# dronetester.net
KiCad netlist of a schematic drawn in EAGLE
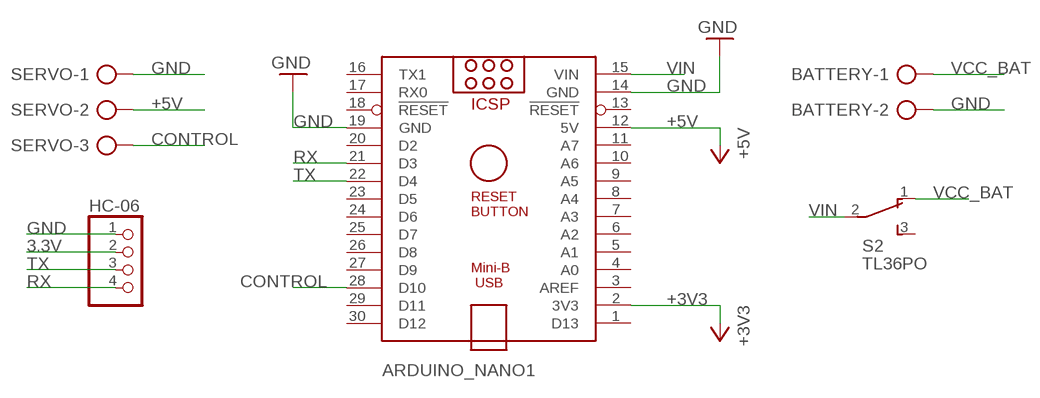
[diagram p0: schematic, sheet 1]

(export (version "E")
  (design (tool "Eeschema 10.0.6"))
  (components
    (comp (ref "ARDUINO_NANO1")
      (value "ARDUINO_NANO")
      (footprint "eagle-import:ARDUINO_NANO")
      (libsource (lib "eagle-import") (part "ARDUINO_NANO"))
    )
    (comp (ref "BATTERY")
      (value "AK500/2-H")
      (footprint "eagle-import:AK500_2-H")
      (libsource (lib "eagle-import") (part "AK500/2-H"))
    )
    (comp (ref "HC-06")
      (value "PINHD-1X4")
      (footprint "eagle-import:1X04")
      (libsource (lib "eagle-import") (part "PINHD-1X4"))
    )
    (comp (ref "S2")
      (value "TL36PO")
      (footprint "eagle-import:TL3XPO")
      (libsource (lib "eagle-import") (part "TL36PO"))
    )
    (comp (ref "SERVO")
      (value "AK500/3-H")
      (footprint "eagle-import:AK500_3-H")
      (libsource (lib "eagle-import") (part "AK500/3-H"))
    )
  )
  (nets
    (net (code "1") (name "+3V3") (class "Default")
      (node (ref "ARDUINO_NANO1") (pin "2") (pinfunction "3V3_2") (pintype "output"))
    )
    (net (code "2") (name "+5V") (class "Default")
      (node (ref "ARDUINO_NANO1") (pin "12") (pinfunction "5V_12") (pintype "power_in"))
      (node (ref "SERVO") (pin "2") (pinfunction "KL_2") (pintype "passive"))
    )
    (net (code "3") (name "/3.3V") (class "Default")
      (node (ref "HC-06") (pin "2") (pinfunction "2_2") (pintype "passive"))
    )
    (net (code "4") (name "/CONTROL") (class "Default")
      (node (ref "ARDUINO_NANO1") (pin "28") (pinfunction "D10_28") (pintype "bidirectional"))
      (node (ref "SERVO") (pin "3") (pinfunction "KL_3") (pintype "passive"))
    )
    (net (code "5") (name "/RX") (class "Default")
      (node (ref "ARDUINO_NANO1") (pin "21") (pinfunction "D3_21") (pintype "bidirectional"))
      (node (ref "HC-06") (pin "4") (pinfunction "4_4") (pintype "passive"))
    )
    (net (code "6") (name "/TX") (class "Default")
      (node (ref "ARDUINO_NANO1") (pin "22") (pinfunction "D4_22") (pintype "bidirectional"))
      (node (ref "HC-06") (pin "3") (pinfunction "3_3") (pintype "passive"))
    )
    (net (code "7") (name "/VCC_BAT") (class "Default")
      (node (ref "BATTERY") (pin "1") (pinfunction "KL_1") (pintype "passive"))
      (node (ref "S2") (pin "1") (pinfunction "O_1") (pintype "passive"))
    )
    (net (code "8") (name "/VIN") (class "Default")
      (node (ref "ARDUINO_NANO1") (pin "15") (pinfunction "VIN_15") (pintype "power_in"))
      (node (ref "S2") (pin "2") (pinfunction "P_2") (pintype "passive"))
    )
    (net (code "9") (name "GND") (class "Default")
      (node (ref "ARDUINO_NANO1") (pin "14") (pinfunction "GND_14") (pintype "power_in"))
      (node (ref "ARDUINO_NANO1") (pin "19") (pinfunction "GND_19") (pintype "power_in"))
      (node (ref "BATTERY") (pin "2") (pinfunction "KL_2") (pintype "passive"))
      (node (ref "HC-06") (pin "1") (pinfunction "1_1") (pintype "passive"))
      (node (ref "SERVO") (pin "1") (pinfunction "KL_1") (pintype "passive"))
    )
    (net (code "10") (name "unconnected-(ARDUINO_NANO1-A0-Pad4)") (class "Default")
      (node (ref "ARDUINO_NANO1") (pin "4") (pinfunction "A0_4") (pintype "bidirectional"))
    )
    (net (code "11") (name "unconnected-(ARDUINO_NANO1-A1-Pad5)") (class "Default")
      (node (ref "ARDUINO_NANO1") (pin "5") (pinfunction "A1_5") (pintype "bidirectional"))
    )
    (net (code "12") (name "unconnected-(ARDUINO_NANO1-A2-Pad6)") (class "Default")
      (node (ref "ARDUINO_NANO1") (pin "6") (pinfunction "A2_6") (pintype "bidirectional"))
    )
    (net (code "13") (name "unconnected-(ARDUINO_NANO1-A3-Pad7)") (class "Default")
      (node (ref "ARDUINO_NANO1") (pin "7") (pinfunction "A3_7") (pintype "bidirectional"))
    )
    (net (code "14") (name "unconnected-(ARDUINO_NANO1-A4-Pad8)") (class "Default")
      (node (ref "ARDUINO_NANO1") (pin "8") (pinfunction "A4_8") (pintype "bidirectional"))
    )
    (net (code "15") (name "unconnected-(ARDUINO_NANO1-A5-Pad9)") (class "Default")
      (node (ref "ARDUINO_NANO1") (pin "9") (pinfunction "A5_9") (pintype "bidirectional"))
    )
    (net (code "16") (name "unconnected-(ARDUINO_NANO1-A6-Pad10)") (class "Default")
      (node (ref "ARDUINO_NANO1") (pin "10") (pinfunction "A6_10") (pintype "bidirectional"))
    )
    (net (code "17") (name "unconnected-(ARDUINO_NANO1-A7-Pad11)") (class "Default")
      (node (ref "ARDUINO_NANO1") (pin "11") (pinfunction "A7_11") (pintype "bidirectional"))
    )
    (net (code "18") (name "unconnected-(ARDUINO_NANO1-AREF-Pad3)") (class "Default")
      (node (ref "ARDUINO_NANO1") (pin "3") (pinfunction "AREF_3") (pintype "input"))
    )
    (net (code "19") (name "unconnected-(ARDUINO_NANO1-D2-Pad20)") (class "Default")
      (node (ref "ARDUINO_NANO1") (pin "20") (pinfunction "D2_20") (pintype "bidirectional"))
    )
    (net (code "20") (name "unconnected-(ARDUINO_NANO1-D5-Pad23)") (class "Default")
      (node (ref "ARDUINO_NANO1") (pin "23") (pinfunction "D5_23") (pintype "bidirectional"))
    )
    (net (code "21") (name "unconnected-(ARDUINO_NANO1-D6-Pad24)") (class "Default")
      (node (ref "ARDUINO_NANO1") (pin "24") (pinfunction "D6_24") (pintype "bidirectional"))
    )
    (net (code "22") (name "unconnected-(ARDUINO_NANO1-D7-Pad25)") (class "Default")
      (node (ref "ARDUINO_NANO1") (pin "25") (pinfunction "D7_25") (pintype "bidirectional"))
    )
    (net (code "23") (name "unconnected-(ARDUINO_NANO1-D8-Pad26)") (class "Default")
      (node (ref "ARDUINO_NANO1") (pin "26") (pinfunction "D8_26") (pintype "bidirectional"))
    )
    (net (code "24") (name "unconnected-(ARDUINO_NANO1-D9-Pad27)") (class "Default")
      (node (ref "ARDUINO_NANO1") (pin "27") (pinfunction "D9_27") (pintype "bidirectional"))
    )
    (net (code "25") (name "unconnected-(ARDUINO_NANO1-D11-Pad29)") (class "Default")
      (node (ref "ARDUINO_NANO1") (pin "29") (pinfunction "D11_29") (pintype "bidirectional"))
    )
    (net (code "26") (name "unconnected-(ARDUINO_NANO1-D12-Pad30)") (class "Default")
      (node (ref "ARDUINO_NANO1") (pin "30") (pinfunction "D12_30") (pintype "bidirectional"))
    )
    (net (code "27") (name "unconnected-(ARDUINO_NANO1-D13-Pad1)") (class "Default")
      (node (ref "ARDUINO_NANO1") (pin "1") (pinfunction "D13_1") (pintype "bidirectional"))
    )
    (net (code "28") (name "unconnected-(ARDUINO_NANO1-RX0-Pad17)") (class "Default")
      (node (ref "ARDUINO_NANO1") (pin "17") (pinfunction "RX0_17") (pintype "bidirectional"))
    )
    (net (code "29") (name "unconnected-(ARDUINO_NANO1-TX1-Pad16)") (class "Default")
      (node (ref "ARDUINO_NANO1") (pin "16") (pinfunction "TX1_16") (pintype "bidirectional"))
    )
    (net (code "30") (name "unconnected-(ARDUINO_NANO1-~{RESET}-Pad13)") (class "Default")
      (node (ref "ARDUINO_NANO1") (pin "13") (pinfunction "~{RESET}_13") (pintype "input"))
    )
    (net (code "31") (name "unconnected-(ARDUINO_NANO1-~{RESET}-Pad18)") (class "Default")
      (node (ref "ARDUINO_NANO1") (pin "18") (pinfunction "~{RESET}_18") (pintype "input"))
    )
    (net (code "32") (name "unconnected-(S2-S-Pad3)") (class "Default")
      (node (ref "S2") (pin "3") (pinfunction "S_3") (pintype "passive"))
    )
  )
)
